# Motor_Control.net
KiCad netlist of a schematic drawn in Altium Designer
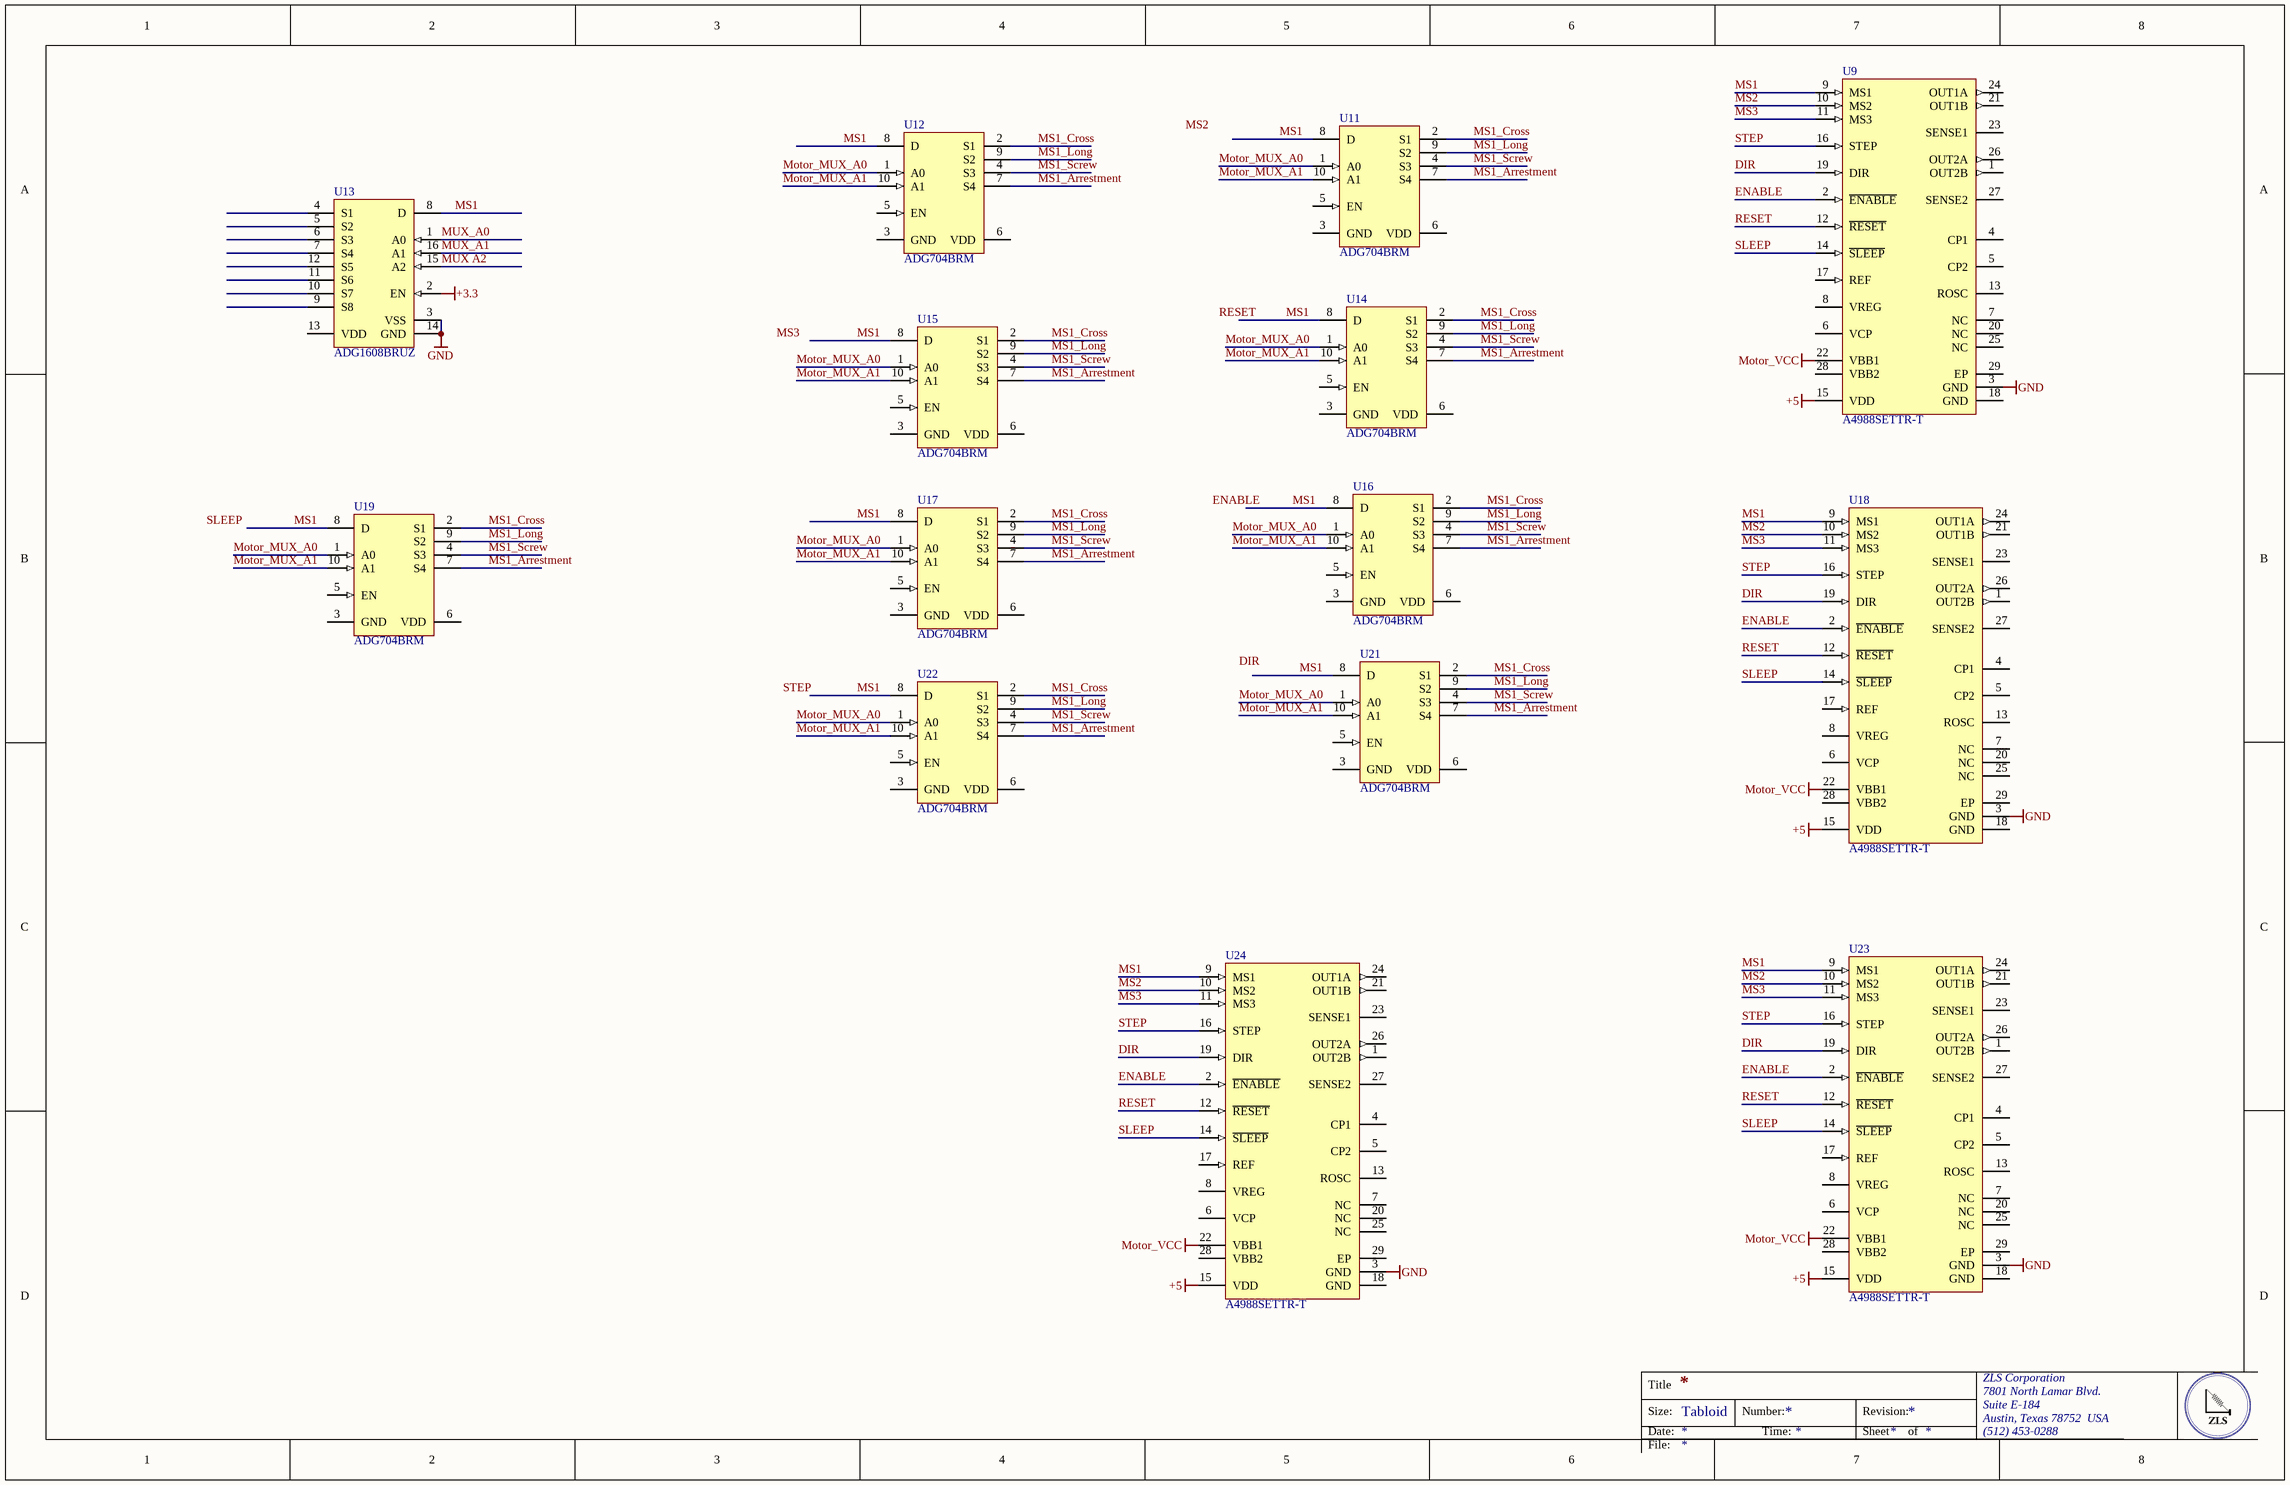
[diagram p0: Motor_Control.SchDoc]

(export (version "E")
  (design (tool "Eeschema 10.0.6"))
  (components
    (comp (ref "U9")
      (value "A4988SETTR-T")
      (footprint "ALEG-ET-28_V")
      (libsource (lib "Altium Content Vault") (part "ALEG-A4988-QFN-28"))
    )
    (comp (ref "U11")
      (value "ADG704BRM")
      (footprint "ADI-RM-10_M")
      (description "CMOS Low Voltage 4 Ohm, 4-Channel Multiplexer, -40 to 85 degC, 10-pin SOP (RM-10), Tube")
      (fields (field (name "MANUFACTURER") "Analog Devices"))
      (libsource (lib "Altium Content Vault") (part "CMP-0798-00102-1"))
    )
    (comp (ref "U12")
      (value "ADG704BRM")
      (footprint "ADI-RM-10_M")
      (description "CMOS Low Voltage 4 Ohm, 4-Channel Multiplexer, -40 to 85 degC, 10-pin SOP (RM-10), Tube")
      (fields (field (name "MANUFACTURER") "Analog Devices"))
      (libsource (lib "Altium Content Vault") (part "CMP-0798-00102-1"))
    )
    (comp (ref "U13")
      (value "ADG1608BRUZ")
      (footprint "ADI-RU-16_M")
      (description "4.5 Ohm Ron, 8-Channel +/-5 V,+12 V, +5 V and +3.3 V Multiplexer, 16-pin SOP (RU-16), Tube")
      (fields (field (name "MANUFACTURER") "Analog Devices"))
      (libsource (lib "Altium Content Vault") (part "ADI-ADG1608-RU-16"))
    )
    (comp (ref "U14")
      (value "ADG704BRM")
      (footprint "ADI-RM-10_M")
      (description "CMOS Low Voltage 4 Ohm, 4-Channel Multiplexer, -40 to 85 degC, 10-pin SOP (RM-10), Tube")
      (fields (field (name "MANUFACTURER") "Analog Devices"))
      (libsource (lib "Altium Content Vault") (part "CMP-0798-00102-1"))
    )
    (comp (ref "U15")
      (value "ADG704BRM")
      (footprint "ADI-RM-10_M")
      (description "CMOS Low Voltage 4 Ohm, 4-Channel Multiplexer, -40 to 85 degC, 10-pin SOP (RM-10), Tube")
      (fields (field (name "MANUFACTURER") "Analog Devices"))
      (libsource (lib "Altium Content Vault") (part "CMP-0798-00102-1"))
    )
    (comp (ref "U16")
      (value "ADG704BRM")
      (footprint "ADI-RM-10_M")
      (description "CMOS Low Voltage 4 Ohm, 4-Channel Multiplexer, -40 to 85 degC, 10-pin SOP (RM-10), Tube")
      (fields (field (name "MANUFACTURER") "Analog Devices"))
      (libsource (lib "Altium Content Vault") (part "CMP-0798-00102-1"))
    )
    (comp (ref "U17")
      (value "ADG704BRM")
      (footprint "ADI-RM-10_M")
      (description "CMOS Low Voltage 4 Ohm, 4-Channel Multiplexer, -40 to 85 degC, 10-pin SOP (RM-10), Tube")
      (fields (field (name "MANUFACTURER") "Analog Devices"))
      (libsource (lib "Altium Content Vault") (part "CMP-0798-00102-1"))
    )
    (comp (ref "U18")
      (value "A4988SETTR-T")
      (footprint "ALEG-ET-28_V")
      (libsource (lib "Altium Content Vault") (part "ALEG-A4988-QFN-28"))
    )
    (comp (ref "U19")
      (value "ADG704BRM")
      (footprint "ADI-RM-10_M")
      (description "CMOS Low Voltage 4 Ohm, 4-Channel Multiplexer, -40 to 85 degC, 10-pin SOP (RM-10), Tube")
      (fields (field (name "MANUFACTURER") "Analog Devices"))
      (libsource (lib "Altium Content Vault") (part "CMP-0798-00102-1"))
    )
    (comp (ref "U21")
      (value "ADG704BRM")
      (footprint "ADI-RM-10_M")
      (description "CMOS Low Voltage 4 Ohm, 4-Channel Multiplexer, -40 to 85 degC, 10-pin SOP (RM-10), Tube")
      (fields (field (name "MANUFACTURER") "Analog Devices"))
      (libsource (lib "Altium Content Vault") (part "CMP-0798-00102-1"))
    )
    (comp (ref "U22")
      (value "ADG704BRM")
      (footprint "ADI-RM-10_M")
      (description "CMOS Low Voltage 4 Ohm, 4-Channel Multiplexer, -40 to 85 degC, 10-pin SOP (RM-10), Tube")
      (fields (field (name "MANUFACTURER") "Analog Devices"))
      (libsource (lib "Altium Content Vault") (part "CMP-0798-00102-1"))
    )
    (comp (ref "U23")
      (value "A4988SETTR-T")
      (footprint "ALEG-ET-28_V")
      (libsource (lib "Altium Content Vault") (part "ALEG-A4988-QFN-28"))
    )
    (comp (ref "U24")
      (value "A4988SETTR-T")
      (footprint "ALEG-ET-28_V")
      (libsource (lib "Altium Content Vault") (part "ALEG-A4988-QFN-28"))
    )
  )
  (nets
    (net (code "1") (name "+3.3") (class "Default")
      (node (ref "U13") (pin "2") (pinfunction "EN_2") (pintype "input"))
    )
    (net (code "2") (name "+5") (class "Default")
      (node (ref "U18") (pin "15") (pinfunction "VDD_15") (pintype "power_in"))
      (node (ref "U23") (pin "15") (pinfunction "VDD_15") (pintype "power_in"))
      (node (ref "U24") (pin "15") (pinfunction "VDD_15") (pintype "power_in"))
      (node (ref "U9") (pin "15") (pinfunction "VDD_15") (pintype "power_in"))
    )
    (net (code "3") (name "/DIR") (class "Default")
      (node (ref "U18") (pin "19") (pinfunction "DIR_19") (pintype "input"))
      (node (ref "U23") (pin "19") (pinfunction "DIR_19") (pintype "input"))
      (node (ref "U24") (pin "19") (pinfunction "DIR_19") (pintype "input"))
      (node (ref "U9") (pin "19") (pinfunction "DIR_19") (pintype "input"))
    )
    (net (code "4") (name "/ENABLE") (class "Default")
      (node (ref "U18") (pin "2") (pinfunction "~{ENABLE}_2") (pintype "input"))
      (node (ref "U23") (pin "2") (pinfunction "~{ENABLE}_2") (pintype "input"))
      (node (ref "U24") (pin "2") (pinfunction "~{ENABLE}_2") (pintype "input"))
      (node (ref "U9") (pin "2") (pinfunction "~{ENABLE}_2") (pintype "input"))
    )
    (net (code "5") (name "/MS1") (class "Default")
      (node (ref "U11") (pin "8") (pinfunction "D_8") (pintype "passive"))
      (node (ref "U12") (pin "8") (pinfunction "D_8") (pintype "passive"))
      (node (ref "U13") (pin "8") (pinfunction "D_8") (pintype "passive"))
      (node (ref "U14") (pin "8") (pinfunction "D_8") (pintype "passive"))
      (node (ref "U15") (pin "8") (pinfunction "D_8") (pintype "passive"))
      (node (ref "U16") (pin "8") (pinfunction "D_8") (pintype "passive"))
      (node (ref "U17") (pin "8") (pinfunction "D_8") (pintype "passive"))
      (node (ref "U18") (pin "9") (pinfunction "MS1_9") (pintype "input"))
      (node (ref "U19") (pin "8") (pinfunction "D_8") (pintype "passive"))
      (node (ref "U21") (pin "8") (pinfunction "D_8") (pintype "passive"))
      (node (ref "U22") (pin "8") (pinfunction "D_8") (pintype "passive"))
      (node (ref "U23") (pin "9") (pinfunction "MS1_9") (pintype "input"))
      (node (ref "U24") (pin "9") (pinfunction "MS1_9") (pintype "input"))
      (node (ref "U9") (pin "9") (pinfunction "MS1_9") (pintype "input"))
    )
    (net (code "6") (name "/MS1_Arrestment") (class "Default")
      (node (ref "U11") (pin "7") (pinfunction "S4_7") (pintype "passive"))
      (node (ref "U12") (pin "7") (pinfunction "S4_7") (pintype "passive"))
      (node (ref "U14") (pin "7") (pinfunction "S4_7") (pintype "passive"))
      (node (ref "U15") (pin "7") (pinfunction "S4_7") (pintype "passive"))
      (node (ref "U16") (pin "7") (pinfunction "S4_7") (pintype "passive"))
      (node (ref "U17") (pin "7") (pinfunction "S4_7") (pintype "passive"))
      (node (ref "U19") (pin "7") (pinfunction "S4_7") (pintype "passive"))
      (node (ref "U21") (pin "7") (pinfunction "S4_7") (pintype "passive"))
      (node (ref "U22") (pin "7") (pinfunction "S4_7") (pintype "passive"))
    )
    (net (code "7") (name "/MS1_Cross") (class "Default")
      (node (ref "U11") (pin "2") (pinfunction "S1_2") (pintype "passive"))
      (node (ref "U12") (pin "2") (pinfunction "S1_2") (pintype "passive"))
      (node (ref "U14") (pin "2") (pinfunction "S1_2") (pintype "passive"))
      (node (ref "U15") (pin "2") (pinfunction "S1_2") (pintype "passive"))
      (node (ref "U16") (pin "2") (pinfunction "S1_2") (pintype "passive"))
      (node (ref "U17") (pin "2") (pinfunction "S1_2") (pintype "passive"))
      (node (ref "U19") (pin "2") (pinfunction "S1_2") (pintype "passive"))
      (node (ref "U21") (pin "2") (pinfunction "S1_2") (pintype "passive"))
      (node (ref "U22") (pin "2") (pinfunction "S1_2") (pintype "passive"))
    )
    (net (code "8") (name "/MS1_Long") (class "Default")
      (node (ref "U11") (pin "9") (pinfunction "S2_9") (pintype "passive"))
      (node (ref "U12") (pin "9") (pinfunction "S2_9") (pintype "passive"))
      (node (ref "U14") (pin "9") (pinfunction "S2_9") (pintype "passive"))
      (node (ref "U15") (pin "9") (pinfunction "S2_9") (pintype "passive"))
      (node (ref "U16") (pin "9") (pinfunction "S2_9") (pintype "passive"))
      (node (ref "U17") (pin "9") (pinfunction "S2_9") (pintype "passive"))
      (node (ref "U19") (pin "9") (pinfunction "S2_9") (pintype "passive"))
      (node (ref "U21") (pin "9") (pinfunction "S2_9") (pintype "passive"))
      (node (ref "U22") (pin "9") (pinfunction "S2_9") (pintype "passive"))
    )
    (net (code "9") (name "/MS1_Screw") (class "Default")
      (node (ref "U11") (pin "4") (pinfunction "S3_4") (pintype "passive"))
      (node (ref "U12") (pin "4") (pinfunction "S3_4") (pintype "passive"))
      (node (ref "U14") (pin "4") (pinfunction "S3_4") (pintype "passive"))
      (node (ref "U15") (pin "4") (pinfunction "S3_4") (pintype "passive"))
      (node (ref "U16") (pin "4") (pinfunction "S3_4") (pintype "passive"))
      (node (ref "U17") (pin "4") (pinfunction "S3_4") (pintype "passive"))
      (node (ref "U19") (pin "4") (pinfunction "S3_4") (pintype "passive"))
      (node (ref "U21") (pin "4") (pinfunction "S3_4") (pintype "passive"))
      (node (ref "U22") (pin "4") (pinfunction "S3_4") (pintype "passive"))
    )
    (net (code "10") (name "/MS2") (class "Default")
      (node (ref "U18") (pin "10") (pinfunction "MS2_10") (pintype "input"))
      (node (ref "U23") (pin "10") (pinfunction "MS2_10") (pintype "input"))
      (node (ref "U24") (pin "10") (pinfunction "MS2_10") (pintype "input"))
      (node (ref "U9") (pin "10") (pinfunction "MS2_10") (pintype "input"))
    )
    (net (code "11") (name "/MS3") (class "Default")
      (node (ref "U18") (pin "11") (pinfunction "MS3_11") (pintype "input"))
      (node (ref "U23") (pin "11") (pinfunction "MS3_11") (pintype "input"))
      (node (ref "U24") (pin "11") (pinfunction "MS3_11") (pintype "input"))
      (node (ref "U9") (pin "11") (pinfunction "MS3_11") (pintype "input"))
    )
    (net (code "12") (name "/MUX A2") (class "Default")
      (node (ref "U13") (pin "15") (pinfunction "A2_15") (pintype "input"))
    )
    (net (code "13") (name "/MUX_A0") (class "Default")
      (node (ref "U13") (pin "1") (pinfunction "A0_1") (pintype "input"))
    )
    (net (code "14") (name "/MUX_A1") (class "Default")
      (node (ref "U13") (pin "16") (pinfunction "A1_16") (pintype "input"))
    )
    (net (code "15") (name "/Motor_MUX_A0") (class "Default")
      (node (ref "U11") (pin "1") (pinfunction "A0_1") (pintype "input"))
      (node (ref "U12") (pin "1") (pinfunction "A0_1") (pintype "input"))
      (node (ref "U14") (pin "1") (pinfunction "A0_1") (pintype "input"))
      (node (ref "U15") (pin "1") (pinfunction "A0_1") (pintype "input"))
      (node (ref "U16") (pin "1") (pinfunction "A0_1") (pintype "input"))
      (node (ref "U17") (pin "1") (pinfunction "A0_1") (pintype "input"))
      (node (ref "U19") (pin "1") (pinfunction "A0_1") (pintype "input"))
      (node (ref "U21") (pin "1") (pinfunction "A0_1") (pintype "input"))
      (node (ref "U22") (pin "1") (pinfunction "A0_1") (pintype "input"))
    )
    (net (code "16") (name "/Motor_MUX_A1") (class "Default")
      (node (ref "U11") (pin "10") (pinfunction "A1_10") (pintype "input"))
      (node (ref "U12") (pin "10") (pinfunction "A1_10") (pintype "input"))
      (node (ref "U14") (pin "10") (pinfunction "A1_10") (pintype "input"))
      (node (ref "U15") (pin "10") (pinfunction "A1_10") (pintype "input"))
      (node (ref "U16") (pin "10") (pinfunction "A1_10") (pintype "input"))
      (node (ref "U17") (pin "10") (pinfunction "A1_10") (pintype "input"))
      (node (ref "U19") (pin "10") (pinfunction "A1_10") (pintype "input"))
      (node (ref "U21") (pin "10") (pinfunction "A1_10") (pintype "input"))
      (node (ref "U22") (pin "10") (pinfunction "A1_10") (pintype "input"))
    )
    (net (code "17") (name "/RESET") (class "Default")
      (node (ref "U18") (pin "12") (pinfunction "~{RESET}_12") (pintype "input"))
      (node (ref "U23") (pin "12") (pinfunction "~{RESET}_12") (pintype "input"))
      (node (ref "U24") (pin "12") (pinfunction "~{RESET}_12") (pintype "input"))
      (node (ref "U9") (pin "12") (pinfunction "~{RESET}_12") (pintype "input"))
    )
    (net (code "18") (name "/SLEEP") (class "Default")
      (node (ref "U18") (pin "14") (pinfunction "~{SLEEP}_14") (pintype "input"))
      (node (ref "U23") (pin "14") (pinfunction "~{SLEEP}_14") (pintype "input"))
      (node (ref "U24") (pin "14") (pinfunction "~{SLEEP}_14") (pintype "input"))
      (node (ref "U9") (pin "14") (pinfunction "~{SLEEP}_14") (pintype "input"))
    )
    (net (code "19") (name "/STEP") (class "Default")
      (node (ref "U18") (pin "16") (pinfunction "STEP_16") (pintype "input"))
      (node (ref "U23") (pin "16") (pinfunction "STEP_16") (pintype "input"))
      (node (ref "U24") (pin "16") (pinfunction "STEP_16") (pintype "input"))
      (node (ref "U9") (pin "16") (pinfunction "STEP_16") (pintype "input"))
    )
    (net (code "20") (name "GND") (class "Default")
      (node (ref "U13") (pin "14") (pinfunction "GND_14") (pintype "power_in"))
      (node (ref "U13") (pin "3") (pinfunction "VSS_3") (pintype "power_in"))
      (node (ref "U18") (pin "3") (pinfunction "GND_3") (pintype "power_in"))
      (node (ref "U23") (pin "3") (pinfunction "GND_3") (pintype "power_in"))
      (node (ref "U24") (pin "3") (pinfunction "GND_3") (pintype "power_in"))
      (node (ref "U9") (pin "3") (pinfunction "GND_3") (pintype "power_in"))
    )
    (net (code "21") (name "Motor_VCC") (class "Default")
      (node (ref "U18") (pin "22") (pinfunction "VBB1_22") (pintype "power_in"))
      (node (ref "U23") (pin "22") (pinfunction "VBB1_22") (pintype "power_in"))
      (node (ref "U24") (pin "22") (pinfunction "VBB1_22") (pintype "power_in"))
      (node (ref "U9") (pin "22") (pinfunction "VBB1_22") (pintype "power_in"))
    )
    (net (code "22") (name "unconnected-(U9-CP1-Pad4)") (class "Default")
      (node (ref "U9") (pin "4") (pinfunction "CP1_4") (pintype "passive"))
    )
    (net (code "23") (name "unconnected-(U9-CP2-Pad5)") (class "Default")
      (node (ref "U9") (pin "5") (pinfunction "CP2_5") (pintype "passive"))
    )
    (net (code "24") (name "unconnected-(U9-EP-Pad29)") (class "Default")
      (node (ref "U9") (pin "29") (pinfunction "EP_29") (pintype "power_in"))
    )
    (net (code "25") (name "unconnected-(U9-GND-Pad18)") (class "Default")
      (node (ref "U9") (pin "18") (pinfunction "GND_18") (pintype "power_in"))
    )
    (net (code "26") (name "unconnected-(U9-NC-Pad7)") (class "Default")
      (node (ref "U9") (pin "7") (pinfunction "NC_7") (pintype "passive"))
    )
    (net (code "27") (name "unconnected-(U9-NC-Pad20)") (class "Default")
      (node (ref "U9") (pin "20") (pinfunction "NC_20") (pintype "passive"))
    )
    (net (code "28") (name "unconnected-(U9-NC-Pad25)") (class "Default")
      (node (ref "U9") (pin "25") (pinfunction "NC_25") (pintype "passive"))
    )
    (net (code "29") (name "unconnected-(U9-OUT1A-Pad24)") (class "Default")
      (node (ref "U9") (pin "24") (pinfunction "OUT1A_24") (pintype "output"))
    )
    (net (code "30") (name "unconnected-(U9-OUT1B-Pad21)") (class "Default")
      (node (ref "U9") (pin "21") (pinfunction "OUT1B_21") (pintype "output"))
    )
    (net (code "31") (name "unconnected-(U9-OUT2A-Pad26)") (class "Default")
      (node (ref "U9") (pin "26") (pinfunction "OUT2A_26") (pintype "output"))
    )
    (net (code "32") (name "unconnected-(U9-OUT2B-Pad1)") (class "Default")
      (node (ref "U9") (pin "1") (pinfunction "OUT2B_1") (pintype "output"))
    )
    (net (code "33") (name "unconnected-(U9-REF-Pad17)") (class "Default")
      (node (ref "U9") (pin "17") (pinfunction "REF_17") (pintype "input"))
    )
    (net (code "34") (name "unconnected-(U9-ROSC-Pad13)") (class "Default")
      (node (ref "U9") (pin "13") (pinfunction "ROSC_13") (pintype "passive"))
    )
    (net (code "35") (name "unconnected-(U9-SENSE1-Pad23)") (class "Default")
      (node (ref "U9") (pin "23") (pinfunction "SENSE1_23") (pintype "passive"))
    )
    (net (code "36") (name "unconnected-(U9-SENSE2-Pad27)") (class "Default")
      (node (ref "U9") (pin "27") (pinfunction "SENSE2_27") (pintype "passive"))
    )
    (net (code "37") (name "unconnected-(U9-VBB2-Pad28)") (class "Default")
      (node (ref "U9") (pin "28") (pinfunction "VBB2_28") (pintype "power_in"))
    )
    (net (code "38") (name "unconnected-(U9-VCP-Pad6)") (class "Default")
      (node (ref "U9") (pin "6") (pinfunction "VCP_6") (pintype "passive"))
    )
    (net (code "39") (name "unconnected-(U9-VREG-Pad8)") (class "Default")
      (node (ref "U9") (pin "8") (pinfunction "VREG_8") (pintype "passive"))
    )
    (net (code "40") (name "unconnected-(U11-EN-Pad5)") (class "Default")
      (node (ref "U11") (pin "5") (pinfunction "EN_5") (pintype "input"))
    )
    (net (code "41") (name "unconnected-(U11-GND-Pad3)") (class "Default")
      (node (ref "U11") (pin "3") (pinfunction "GND_3") (pintype "power_in"))
    )
    (net (code "42") (name "unconnected-(U11-VDD-Pad6)") (class "Default")
      (node (ref "U11") (pin "6") (pinfunction "VDD_6") (pintype "power_in"))
    )
    (net (code "43") (name "unconnected-(U12-EN-Pad5)") (class "Default")
      (node (ref "U12") (pin "5") (pinfunction "EN_5") (pintype "input"))
    )
    (net (code "44") (name "unconnected-(U12-GND-Pad3)") (class "Default")
      (node (ref "U12") (pin "3") (pinfunction "GND_3") (pintype "power_in"))
    )
    (net (code "45") (name "unconnected-(U12-VDD-Pad6)") (class "Default")
      (node (ref "U12") (pin "6") (pinfunction "VDD_6") (pintype "power_in"))
    )
    (net (code "46") (name "unconnected-(U13-S1-Pad4)") (class "Default")
      (node (ref "U13") (pin "4") (pinfunction "S1_4") (pintype "passive"))
    )
    (net (code "47") (name "unconnected-(U13-S2-Pad5)") (class "Default")
      (node (ref "U13") (pin "5") (pinfunction "S2_5") (pintype "passive"))
    )
    (net (code "48") (name "unconnected-(U13-S3-Pad6)") (class "Default")
      (node (ref "U13") (pin "6") (pinfunction "S3_6") (pintype "passive"))
    )
    (net (code "49") (name "unconnected-(U13-S4-Pad7)") (class "Default")
      (node (ref "U13") (pin "7") (pinfunction "S4_7") (pintype "passive"))
    )
    (net (code "50") (name "unconnected-(U13-S5-Pad12)") (class "Default")
      (node (ref "U13") (pin "12") (pinfunction "S5_12") (pintype "passive"))
    )
    (net (code "51") (name "unconnected-(U13-S6-Pad11)") (class "Default")
      (node (ref "U13") (pin "11") (pinfunction "S6_11") (pintype "passive"))
    )
    (net (code "52") (name "unconnected-(U13-S7-Pad10)") (class "Default")
      (node (ref "U13") (pin "10") (pinfunction "S7_10") (pintype "passive"))
    )
    (net (code "53") (name "unconnected-(U13-S8-Pad9)") (class "Default")
      (node (ref "U13") (pin "9") (pinfunction "S8_9") (pintype "passive"))
    )
    (net (code "54") (name "unconnected-(U13-VDD-Pad13)") (class "Default")
      (node (ref "U13") (pin "13") (pinfunction "VDD_13") (pintype "power_in"))
    )
    (net (code "55") (name "unconnected-(U14-EN-Pad5)") (class "Default")
      (node (ref "U14") (pin "5") (pinfunction "EN_5") (pintype "input"))
    )
    (net (code "56") (name "unconnected-(U14-GND-Pad3)") (class "Default")
      (node (ref "U14") (pin "3") (pinfunction "GND_3") (pintype "power_in"))
    )
    (net (code "57") (name "unconnected-(U14-VDD-Pad6)") (class "Default")
      (node (ref "U14") (pin "6") (pinfunction "VDD_6") (pintype "power_in"))
    )
    (net (code "58") (name "unconnected-(U15-EN-Pad5)") (class "Default")
      (node (ref "U15") (pin "5") (pinfunction "EN_5") (pintype "input"))
    )
    (net (code "59") (name "unconnected-(U15-GND-Pad3)") (class "Default")
      (node (ref "U15") (pin "3") (pinfunction "GND_3") (pintype "power_in"))
    )
    (net (code "60") (name "unconnected-(U15-VDD-Pad6)") (class "Default")
      (node (ref "U15") (pin "6") (pinfunction "VDD_6") (pintype "power_in"))
    )
    (net (code "61") (name "unconnected-(U16-EN-Pad5)") (class "Default")
      (node (ref "U16") (pin "5") (pinfunction "EN_5") (pintype "input"))
    )
    (net (code "62") (name "unconnected-(U16-GND-Pad3)") (class "Default")
      (node (ref "U16") (pin "3") (pinfunction "GND_3") (pintype "power_in"))
    )
    (net (code "63") (name "unconnected-(U16-VDD-Pad6)") (class "Default")
      (node (ref "U16") (pin "6") (pinfunction "VDD_6") (pintype "power_in"))
    )
    (net (code "64") (name "unconnected-(U17-EN-Pad5)") (class "Default")
      (node (ref "U17") (pin "5") (pinfunction "EN_5") (pintype "input"))
    )
    (net (code "65") (name "unconnected-(U17-GND-Pad3)") (class "Default")
      (node (ref "U17") (pin "3") (pinfunction "GND_3") (pintype "power_in"))
    )
    (net (code "66") (name "unconnected-(U17-VDD-Pad6)") (class "Default")
      (node (ref "U17") (pin "6") (pinfunction "VDD_6") (pintype "power_in"))
    )
    (net (code "67") (name "unconnected-(U18-CP1-Pad4)") (class "Default")
      (node (ref "U18") (pin "4") (pinfunction "CP1_4") (pintype "passive"))
    )
    (net (code "68") (name "unconnected-(U18-CP2-Pad5)") (class "Default")
      (node (ref "U18") (pin "5") (pinfunction "CP2_5") (pintype "passive"))
    )
    (net (code "69") (name "unconnected-(U18-EP-Pad29)") (class "Default")
      (node (ref "U18") (pin "29") (pinfunction "EP_29") (pintype "power_in"))
    )
    (net (code "70") (name "unconnected-(U18-GND-Pad18)") (class "Default")
      (node (ref "U18") (pin "18") (pinfunction "GND_18") (pintype "power_in"))
    )
    (net (code "71") (name "unconnected-(U18-NC-Pad7)") (class "Default")
      (node (ref "U18") (pin "7") (pinfunction "NC_7") (pintype "passive"))
    )
    (net (code "72") (name "unconnected-(U18-NC-Pad20)") (class "Default")
      (node (ref "U18") (pin "20") (pinfunction "NC_20") (pintype "passive"))
    )
    (net (code "73") (name "unconnected-(U18-NC-Pad25)") (class "Default")
      (node (ref "U18") (pin "25") (pinfunction "NC_25") (pintype "passive"))
    )
    (net (code "74") (name "unconnected-(U18-OUT1A-Pad24)") (class "Default")
      (node (ref "U18") (pin "24") (pinfunction "OUT1A_24") (pintype "output"))
    )
    (net (code "75") (name "unconnected-(U18-OUT1B-Pad21)") (class "Default")
      (node (ref "U18") (pin "21") (pinfunction "OUT1B_21") (pintype "output"))
    )
    (net (code "76") (name "unconnected-(U18-OUT2A-Pad26)") (class "Default")
      (node (ref "U18") (pin "26") (pinfunction "OUT2A_26") (pintype "output"))
    )
    (net (code "77") (name "unconnected-(U18-OUT2B-Pad1)") (class "Default")
      (node (ref "U18") (pin "1") (pinfunction "OUT2B_1") (pintype "output"))
    )
    (net (code "78") (name "unconnected-(U18-REF-Pad17)") (class "Default")
      (node (ref "U18") (pin "17") (pinfunction "REF_17") (pintype "input"))
    )
    (net (code "79") (name "unconnected-(U18-ROSC-Pad13)") (class "Default")
      (node (ref "U18") (pin "13") (pinfunction "ROSC_13") (pintype "passive"))
    )
    (net (code "80") (name "unconnected-(U18-SENSE1-Pad23)") (class "Default")
      (node (ref "U18") (pin "23") (pinfunction "SENSE1_23") (pintype "passive"))
    )
    (net (code "81") (name "unconnected-(U18-SENSE2-Pad27)") (class "Default")
      (node (ref "U18") (pin "27") (pinfunction "SENSE2_27") (pintype "passive"))
    )
    (net (code "82") (name "unconnected-(U18-VBB2-Pad28)") (class "Default")
      (node (ref "U18") (pin "28") (pinfunction "VBB2_28") (pintype "power_in"))
    )
    (net (code "83") (name "unconnected-(U18-VCP-Pad6)") (class "Default")
      (node (ref "U18") (pin "6") (pinfunction "VCP_6") (pintype "passive"))
    )
    (net (code "84") (name "unconnected-(U18-VREG-Pad8)") (class "Default")
      (node (ref "U18") (pin "8") (pinfunction "VREG_8") (pintype "passive"))
    )
    (net (code "85") (name "unconnected-(U19-EN-Pad5)") (class "Default")
      (node (ref "U19") (pin "5") (pinfunction "EN_5") (pintype "input"))
    )
    (net (code "86") (name "unconnected-(U19-GND-Pad3)") (class "Default")
      (node (ref "U19") (pin "3") (pinfunction "GND_3") (pintype "power_in"))
    )
    (net (code "87") (name "unconnected-(U19-VDD-Pad6)") (class "Default")
      (node (ref "U19") (pin "6") (pinfunction "VDD_6") (pintype "power_in"))
    )
    (net (code "88") (name "unconnected-(U21-EN-Pad5)") (class "Default")
      (node (ref "U21") (pin "5") (pinfunction "EN_5") (pintype "input"))
    )
    (net (code "89") (name "unconnected-(U21-GND-Pad3)") (class "Default")
      (node (ref "U21") (pin "3") (pinfunction "GND_3") (pintype "power_in"))
    )
    (net (code "90") (name "unconnected-(U21-VDD-Pad6)") (class "Default")
      (node (ref "U21") (pin "6") (pinfunction "VDD_6") (pintype "power_in"))
    )
    (net (code "91") (name "unconnected-(U22-EN-Pad5)") (class "Default")
      (node (ref "U22") (pin "5") (pinfunction "EN_5") (pintype "input"))
    )
    (net (code "92") (name "unconnected-(U22-GND-Pad3)") (class "Default")
      (node (ref "U22") (pin "3") (pinfunction "GND_3") (pintype "power_in"))
    )
    (net (code "93") (name "unconnected-(U22-VDD-Pad6)") (class "Default")
      (node (ref "U22") (pin "6") (pinfunction "VDD_6") (pintype "power_in"))
    )
    (net (code "94") (name "unconnected-(U23-CP1-Pad4)") (class "Default")
      (node (ref "U23") (pin "4") (pinfunction "CP1_4") (pintype "passive"))
    )
    (net (code "95") (name "unconnected-(U23-CP2-Pad5)") (class "Default")
      (node (ref "U23") (pin "5") (pinfunction "CP2_5") (pintype "passive"))
    )
    (net (code "96") (name "unconnected-(U23-EP-Pad29)") (class "Default")
      (node (ref "U23") (pin "29") (pinfunction "EP_29") (pintype "power_in"))
    )
    (net (code "97") (name "unconnected-(U23-GND-Pad18)") (class "Default")
      (node (ref "U23") (pin "18") (pinfunction "GND_18") (pintype "power_in"))
    )
    (net (code "98") (name "unconnected-(U23-NC-Pad7)") (class "Default")
      (node (ref "U23") (pin "7") (pinfunction "NC_7") (pintype "passive"))
    )
    (net (code "99") (name "unconnected-(U23-NC-Pad20)") (class "Default")
      (node (ref "U23") (pin "20") (pinfunction "NC_20") (pintype "passive"))
    )
    (net (code "100") (name "unconnected-(U23-NC-Pad25)") (class "Default")
      (node (ref "U23") (pin "25") (pinfunction "NC_25") (pintype "passive"))
    )
    (net (code "101") (name "unconnected-(U23-OUT1A-Pad24)") (class "Default")
      (node (ref "U23") (pin "24") (pinfunction "OUT1A_24") (pintype "output"))
    )
    (net (code "102") (name "unconnected-(U23-OUT1B-Pad21)") (class "Default")
      (node (ref "U23") (pin "21") (pinfunction "OUT1B_21") (pintype "output"))
    )
    (net (code "103") (name "unconnected-(U23-OUT2A-Pad26)") (class "Default")
      (node (ref "U23") (pin "26") (pinfunction "OUT2A_26") (pintype "output"))
    )
    (net (code "104") (name "unconnected-(U23-OUT2B-Pad1)") (class "Default")
      (node (ref "U23") (pin "1") (pinfunction "OUT2B_1") (pintype "output"))
    )
    (net (code "105") (name "unconnected-(U23-REF-Pad17)") (class "Default")
      (node (ref "U23") (pin "17") (pinfunction "REF_17") (pintype "input"))
    )
    (net (code "106") (name "unconnected-(U23-ROSC-Pad13)") (class "Default")
      (node (ref "U23") (pin "13") (pinfunction "ROSC_13") (pintype "passive"))
    )
    (net (code "107") (name "unconnected-(U23-SENSE1-Pad23)") (class "Default")
      (node (ref "U23") (pin "23") (pinfunction "SENSE1_23") (pintype "passive"))
    )
    (net (code "108") (name "unconnected-(U23-SENSE2-Pad27)") (class "Default")
      (node (ref "U23") (pin "27") (pinfunction "SENSE2_27") (pintype "passive"))
    )
    (net (code "109") (name "unconnected-(U23-VBB2-Pad28)") (class "Default")
      (node (ref "U23") (pin "28") (pinfunction "VBB2_28") (pintype "power_in"))
    )
    (net (code "110") (name "unconnected-(U23-VCP-Pad6)") (class "Default")
      (node (ref "U23") (pin "6") (pinfunction "VCP_6") (pintype "passive"))
    )
    (net (code "111") (name "unconnected-(U23-VREG-Pad8)") (class "Default")
      (node (ref "U23") (pin "8") (pinfunction "VREG_8") (pintype "passive"))
    )
    (net (code "112") (name "unconnected-(U24-CP1-Pad4)") (class "Default")
      (node (ref "U24") (pin "4") (pinfunction "CP1_4") (pintype "passive"))
    )
    (net (code "113") (name "unconnected-(U24-CP2-Pad5)") (class "Default")
      (node (ref "U24") (pin "5") (pinfunction "CP2_5") (pintype "passive"))
    )
    (net (code "114") (name "unconnected-(U24-EP-Pad29)") (class "Default")
      (node (ref "U24") (pin "29") (pinfunction "EP_29") (pintype "power_in"))
    )
    (net (code "115") (name "unconnected-(U24-GND-Pad18)") (class "Default")
      (node (ref "U24") (pin "18") (pinfunction "GND_18") (pintype "power_in"))
    )
    (net (code "116") (name "unconnected-(U24-NC-Pad7)") (class "Default")
      (node (ref "U24") (pin "7") (pinfunction "NC_7") (pintype "passive"))
    )
    (net (code "117") (name "unconnected-(U24-NC-Pad20)") (class "Default")
      (node (ref "U24") (pin "20") (pinfunction "NC_20") (pintype "passive"))
    )
    (net (code "118") (name "unconnected-(U24-NC-Pad25)") (class "Default")
      (node (ref "U24") (pin "25") (pinfunction "NC_25") (pintype "passive"))
    )
    (net (code "119") (name "unconnected-(U24-OUT1A-Pad24)") (class "Default")
      (node (ref "U24") (pin "24") (pinfunction "OUT1A_24") (pintype "output"))
    )
    (net (code "120") (name "unconnected-(U24-OUT1B-Pad21)") (class "Default")
      (node (ref "U24") (pin "21") (pinfunction "OUT1B_21") (pintype "output"))
    )
    (net (code "121") (name "unconnected-(U24-OUT2A-Pad26)") (class "Default")
      (node (ref "U24") (pin "26") (pinfunction "OUT2A_26") (pintype "output"))
    )
    (net (code "122") (name "unconnected-(U24-OUT2B-Pad1)") (class "Default")
      (node (ref "U24") (pin "1") (pinfunction "OUT2B_1") (pintype "output"))
    )
    (net (code "123") (name "unconnected-(U24-REF-Pad17)") (class "Default")
      (node (ref "U24") (pin "17") (pinfunction "REF_17") (pintype "input"))
    )
    (net (code "124") (name "unconnected-(U24-ROSC-Pad13)") (class "Default")
      (node (ref "U24") (pin "13") (pinfunction "ROSC_13") (pintype "passive"))
    )
    (net (code "125") (name "unconnected-(U24-SENSE1-Pad23)") (class "Default")
      (node (ref "U24") (pin "23") (pinfunction "SENSE1_23") (pintype "passive"))
    )
    (net (code "126") (name "unconnected-(U24-SENSE2-Pad27)") (class "Default")
      (node (ref "U24") (pin "27") (pinfunction "SENSE2_27") (pintype "passive"))
    )
    (net (code "127") (name "unconnected-(U24-VBB2-Pad28)") (class "Default")
      (node (ref "U24") (pin "28") (pinfunction "VBB2_28") (pintype "power_in"))
    )
    (net (code "128") (name "unconnected-(U24-VCP-Pad6)") (class "Default")
      (node (ref "U24") (pin "6") (pinfunction "VCP_6") (pintype "passive"))
    )
    (net (code "129") (name "unconnected-(U24-VREG-Pad8)") (class "Default")
      (node (ref "U24") (pin "8") (pinfunction "VREG_8") (pintype "passive"))
    )
  )
)
